# eDP_DLT.net
KiCad netlist of a schematic drawn in EAGLE
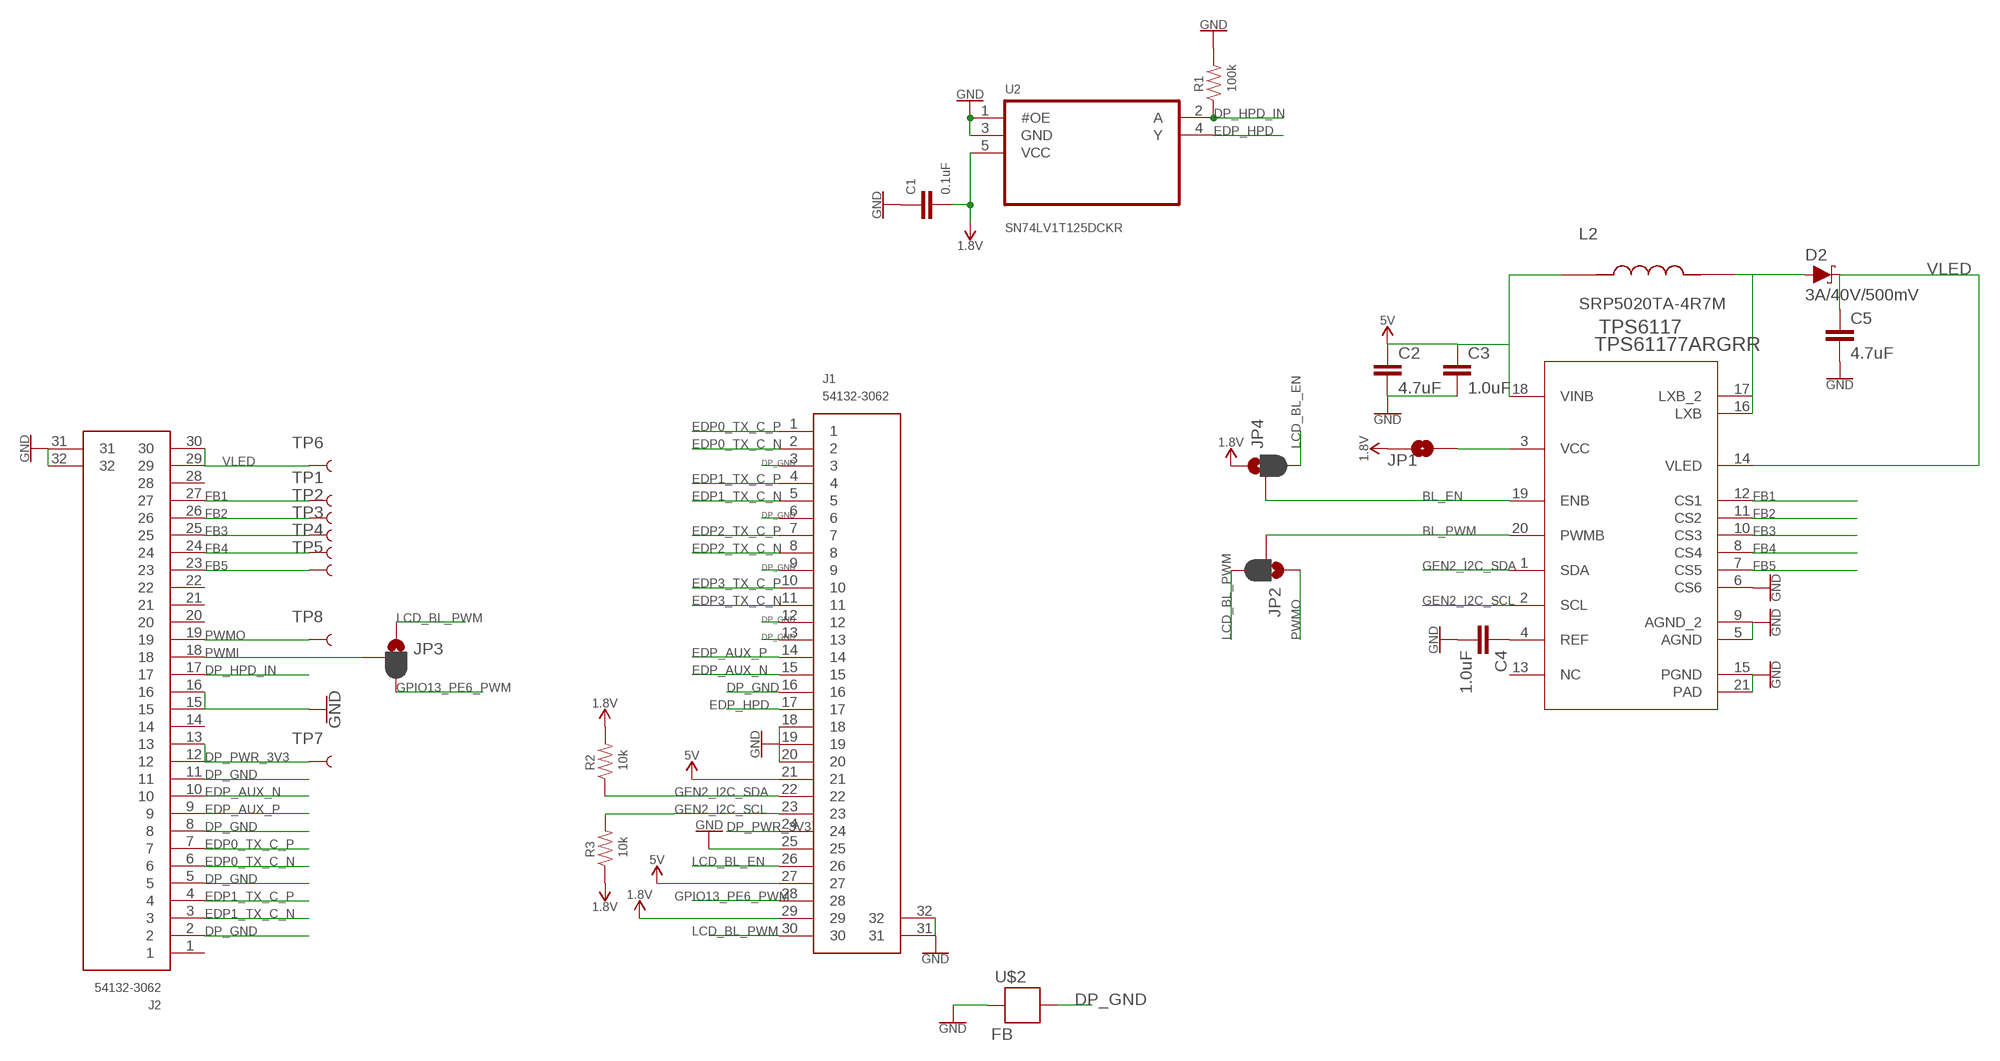
[diagram p0: schematic, sheet 1]

(export (version "E")
  (design (tool "Eeschema 10.0.6"))
  (components
    (comp (ref "C1")
      (value "0.1uF")
      (footprint "eagle-import:0603")
      (libsource (lib "eagle-import") (part "10NF-0603-50V-10%"))
    )
    (comp (ref "C2")
      (value "4.7uF")
      (footprint "eagle-import:0603")
      (libsource (lib "eagle-import") (part "4.7UF0603"))
    )
    (comp (ref "C3")
      (value "1.0uF")
      (footprint "eagle-import:0603")
      (libsource (lib "eagle-import") (part "1.0UF-0603-16V-10%"))
    )
    (comp (ref "C4")
      (value "1.0uF")
      (footprint "eagle-import:0603")
      (libsource (lib "eagle-import") (part "1.0UF-0603-16V-10%"))
    )
    (comp (ref "C5")
      (value "4.7uF")
      (footprint "eagle-import:0603")
      (libsource (lib "eagle-import") (part "4.7UF0603"))
    )
    (comp (ref "D2")
      (value "3A/40V/500mV")
      (footprint "eagle-import:SMA-DIODE")
      (libsource (lib "eagle-import") (part "DIODE-SCHOTTKY-B340A"))
    )
    (comp (ref "J1")
      (value "54132-3062")
      (footprint "eagle-import:54132-3062")
      (fields (field (name "MOUSER_PART_NUMBER") "538-54132-3062"))
      (libsource (lib "eagle-import") (part "54132-3062"))
    )
    (comp (ref "J2")
      (value "54132-3062")
      (footprint "eagle-import:54132-3062")
      (fields (field (name "MOUSER_PART_NUMBER") "538-54132-3062"))
      (libsource (lib "eagle-import") (part "54132-3062"))
    )
    (comp (ref "JP1")
      (value "JUMPER-SMT_2_NO_NO-SILK")
      (footprint "eagle-import:SMT-JUMPER_2_NO_NO-SILK")
      (libsource (lib "eagle-import") (part "JUMPER-SMT_2_NO_NO-SILK"))
    )
    (comp (ref "JP2")
      (value "JUMPER-SMT_3_1-NC_PASTE_NO-SILK")
      (footprint "eagle-import:SMT-JUMPER_3_1-NC_PASTE_NO-SILK")
      (libsource (lib "eagle-import") (part "JUMPER-SMT_3_1-NC_PASTE_NO-SILK"))
    )
    (comp (ref "JP3")
      (value "JUMPER-SMT_3_1-NC_PASTE_NO-SILK")
      (footprint "eagle-import:SMT-JUMPER_3_1-NC_PASTE_NO-SILK")
      (libsource (lib "eagle-import") (part "JUMPER-SMT_3_1-NC_PASTE_NO-SILK"))
    )
    (comp (ref "JP4")
      (value "JUMPER-SMT_3_1-NC_PASTE_NO-SILK")
      (footprint "eagle-import:SMT-JUMPER_3_1-NC_PASTE_NO-SILK")
      (libsource (lib "eagle-import") (part "JUMPER-SMT_3_1-NC_PASTE_NO-SILK"))
    )
    (comp (ref "L2")
      (value "SRP5020TA-4R7M")
      (footprint "eagle-import:IND_SRP5020TA-4R7M")
      (fields (field (name "MF") "Bourns"))
      (libsource (lib "eagle-import") (part "SRP5020TA-4R7M"))
    )
    (comp (ref "R1")
      (value "100k")
      (footprint "eagle-import:0603-RES")
      (libsource (lib "eagle-import") (part "RESISTOR0603-RES"))
    )
    (comp (ref "R2")
      (value "10k")
      (footprint "eagle-import:0603-RES")
      (libsource (lib "eagle-import") (part "RESISTOR0603-RES"))
    )
    (comp (ref "R3")
      (value "10k")
      (footprint "eagle-import:0603-RES")
      (libsource (lib "eagle-import") (part "RESISTOR0603-RES"))
    )
    (comp (ref "TP1")
      (value "TEST-POINT3")
      (footprint "eagle-import:PAD.03X.03")
      (libsource (lib "eagle-import") (part "TEST-POINT3"))
    )
    (comp (ref "TP2")
      (value "TEST-POINT3")
      (footprint "eagle-import:PAD.03X.03")
      (libsource (lib "eagle-import") (part "TEST-POINT3"))
    )
    (comp (ref "TP3")
      (value "TEST-POINT3")
      (footprint "eagle-import:PAD.03X.03")
      (libsource (lib "eagle-import") (part "TEST-POINT3"))
    )
    (comp (ref "TP4")
      (value "TEST-POINT3")
      (footprint "eagle-import:PAD.03X.03")
      (libsource (lib "eagle-import") (part "TEST-POINT3"))
    )
    (comp (ref "TP5")
      (value "TEST-POINT3")
      (footprint "eagle-import:PAD.03X.03")
      (libsource (lib "eagle-import") (part "TEST-POINT3"))
    )
    (comp (ref "TP6")
      (value "TEST-POINT3")
      (footprint "eagle-import:PAD.03X.03")
      (libsource (lib "eagle-import") (part "TEST-POINT3"))
    )
    (comp (ref "TP7")
      (value "TEST-POINT3")
      (footprint "eagle-import:PAD.03X.03")
      (libsource (lib "eagle-import") (part "TEST-POINT3"))
    )
    (comp (ref "TP8")
      (value "TEST-POINT3")
      (footprint "eagle-import:PAD.03X.03")
      (libsource (lib "eagle-import") (part "TEST-POINT3"))
    )
    (comp (ref "TPS6117")
      (value "TPS61177ARGRR")
      (footprint "eagle-import:RGR0020A")
      (libsource (lib "eagle-import") (part "TPS61177ARGRR"))
    )
    (comp (ref "U$2")
      (value "FB")
      (footprint "eagle-import:0603")
      (libsource (lib "eagle-import") (part "FB"))
    )
    (comp (ref "U2")
      (value "SN74LV1T125DCKR")
      (footprint "eagle-import:SOT65P210X110-5N")
      (fields (field (name "MF") "Texas Instruments"))
      (libsource (lib "eagle-import") (part "SN74LV1T125DCKR"))
    )
  )
  (nets
    (net (code "1") (name "/BL_EN") (class "Default")
      (node (ref "JP4") (pin "2") (pinfunction "2_2") (pintype "passive"))
      (node (ref "TPS6117") (pin "19") (pinfunction "ENB_19") (pintype "input"))
    )
    (net (code "2") (name "/BL_PWM") (class "Default")
      (node (ref "JP2") (pin "2") (pinfunction "2_2") (pintype "passive"))
      (node (ref "TPS6117") (pin "20") (pinfunction "PWMB_20") (pintype "input"))
    )
    (net (code "3") (name "/DP_GND") (class "Default")
      (node (ref "J1") (pin "12") (pinfunction "12_12") (pintype "bidirectional"))
      (node (ref "J1") (pin "13") (pinfunction "13_13") (pintype "bidirectional"))
      (node (ref "J1") (pin "16") (pinfunction "16_16") (pintype "bidirectional"))
      (node (ref "J1") (pin "3") (pinfunction "3_3") (pintype "bidirectional"))
      (node (ref "J1") (pin "6") (pinfunction "6_6") (pintype "bidirectional"))
      (node (ref "J1") (pin "9") (pinfunction "9_9") (pintype "bidirectional"))
      (node (ref "J2") (pin "11") (pinfunction "11_11") (pintype "bidirectional"))
      (node (ref "J2") (pin "2") (pinfunction "2_2") (pintype "bidirectional"))
      (node (ref "J2") (pin "5") (pinfunction "5_5") (pintype "bidirectional"))
      (node (ref "J2") (pin "8") (pinfunction "8_8") (pintype "bidirectional"))
      (node (ref "U$2") (pin "1") (pinfunction "P$1_1") (pintype "bidirectional"))
    )
    (net (code "4") (name "/DP_HPD_IN") (class "Default")
      (node (ref "J2") (pin "17") (pinfunction "17_17") (pintype "bidirectional"))
      (node (ref "R1") (pin "1") (pinfunction "1_1") (pintype "passive"))
      (node (ref "U2") (pin "2") (pinfunction "A_2") (pintype "output"))
    )
    (net (code "5") (name "/DP_PWR_3V3") (class "Default")
      (node (ref "J1") (pin "24") (pinfunction "24_24") (pintype "bidirectional"))
      (node (ref "J2") (pin "12") (pinfunction "12_12") (pintype "bidirectional"))
      (node (ref "J2") (pin "13") (pinfunction "13_13") (pintype "bidirectional"))
      (node (ref "TP7") (pin "P$1") (pinfunction "1_P$1") (pintype "bidirectional"))
    )
    (net (code "6") (name "/EDP0_TX_C_N") (class "Default")
      (node (ref "J1") (pin "2") (pinfunction "2_2") (pintype "bidirectional"))
      (node (ref "J2") (pin "6") (pinfunction "6_6") (pintype "bidirectional"))
    )
    (net (code "7") (name "/EDP0_TX_C_P") (class "Default")
      (node (ref "J1") (pin "1") (pinfunction "1_1") (pintype "bidirectional"))
      (node (ref "J2") (pin "7") (pinfunction "7_7") (pintype "bidirectional"))
    )
    (net (code "8") (name "/EDP1_TX_C_N") (class "Default")
      (node (ref "J1") (pin "5") (pinfunction "5_5") (pintype "bidirectional"))
      (node (ref "J2") (pin "3") (pinfunction "3_3") (pintype "bidirectional"))
    )
    (net (code "9") (name "/EDP1_TX_C_P") (class "Default")
      (node (ref "J1") (pin "4") (pinfunction "4_4") (pintype "bidirectional"))
      (node (ref "J2") (pin "4") (pinfunction "4_4") (pintype "bidirectional"))
    )
    (net (code "10") (name "/EDP2_TX_C_N") (class "Default")
      (node (ref "J1") (pin "8") (pinfunction "8_8") (pintype "bidirectional"))
    )
    (net (code "11") (name "/EDP2_TX_C_P") (class "Default")
      (node (ref "J1") (pin "7") (pinfunction "7_7") (pintype "bidirectional"))
    )
    (net (code "12") (name "/EDP3_TX_C_N") (class "Default")
      (node (ref "J1") (pin "11") (pinfunction "11_11") (pintype "bidirectional"))
    )
    (net (code "13") (name "/EDP3_TX_C_P") (class "Default")
      (node (ref "J1") (pin "10") (pinfunction "10_10") (pintype "bidirectional"))
    )
    (net (code "14") (name "/EDP_AUX_N") (class "Default")
      (node (ref "J1") (pin "15") (pinfunction "15_15") (pintype "bidirectional"))
      (node (ref "J2") (pin "10") (pinfunction "10_10") (pintype "bidirectional"))
    )
    (net (code "15") (name "/EDP_AUX_P") (class "Default")
      (node (ref "J1") (pin "14") (pinfunction "14_14") (pintype "bidirectional"))
      (node (ref "J2") (pin "9") (pinfunction "9_9") (pintype "bidirectional"))
    )
    (net (code "16") (name "/EDP_HPD") (class "Default")
      (node (ref "J1") (pin "17") (pinfunction "17_17") (pintype "bidirectional"))
      (node (ref "U2") (pin "4") (pinfunction "Y_4") (pintype "output"))
    )
    (net (code "17") (name "/FB1") (class "Default")
      (node (ref "J2") (pin "27") (pinfunction "27_27") (pintype "bidirectional"))
      (node (ref "TP1") (pin "P$1") (pinfunction "1_P$1") (pintype "bidirectional"))
      (node (ref "TPS6117") (pin "12") (pinfunction "CS1_12") (pintype "power_in"))
    )
    (net (code "18") (name "/FB2") (class "Default")
      (node (ref "J2") (pin "26") (pinfunction "26_26") (pintype "bidirectional"))
      (node (ref "TP2") (pin "P$1") (pinfunction "1_P$1") (pintype "bidirectional"))
      (node (ref "TPS6117") (pin "11") (pinfunction "CS2_11") (pintype "power_in"))
    )
    (net (code "19") (name "/FB3") (class "Default")
      (node (ref "J2") (pin "25") (pinfunction "25_25") (pintype "bidirectional"))
      (node (ref "TP3") (pin "P$1") (pinfunction "1_P$1") (pintype "bidirectional"))
      (node (ref "TPS6117") (pin "10") (pinfunction "CS3_10") (pintype "power_in"))
    )
    (net (code "20") (name "/FB4") (class "Default")
      (node (ref "J2") (pin "24") (pinfunction "24_24") (pintype "bidirectional"))
      (node (ref "TP4") (pin "P$1") (pinfunction "1_P$1") (pintype "bidirectional"))
      (node (ref "TPS6117") (pin "8") (pinfunction "CS4_8") (pintype "power_in"))
    )
    (net (code "21") (name "/FB5") (class "Default")
      (node (ref "J2") (pin "23") (pinfunction "23_23") (pintype "bidirectional"))
      (node (ref "TP5") (pin "P$1") (pinfunction "1_P$1") (pintype "bidirectional"))
      (node (ref "TPS6117") (pin "7") (pinfunction "CS5_7") (pintype "power_in"))
    )
    (net (code "22") (name "/GEN2_I2C_SCL") (class "Default")
      (node (ref "J1") (pin "23") (pinfunction "23_23") (pintype "bidirectional"))
      (node (ref "R3") (pin "2") (pinfunction "2_2") (pintype "passive"))
      (node (ref "TPS6117") (pin "2") (pinfunction "SCL_2") (pintype "input"))
    )
    (net (code "23") (name "/GEN2_I2C_SDA") (class "Default")
      (node (ref "J1") (pin "22") (pinfunction "22_22") (pintype "bidirectional"))
      (node (ref "R2") (pin "1") (pinfunction "1_1") (pintype "passive"))
      (node (ref "TPS6117") (pin "1") (pinfunction "SDA_1") (pintype "input"))
    )
    (net (code "24") (name "/GPIO13_PE6_PWM") (class "Default")
      (node (ref "J1") (pin "28") (pinfunction "28_28") (pintype "bidirectional"))
      (node (ref "JP3") (pin "3") (pinfunction "3_3") (pintype "passive"))
    )
    (net (code "25") (name "/LCD_BL_EN") (class "Default")
      (node (ref "J1") (pin "26") (pinfunction "26_26") (pintype "bidirectional"))
      (node (ref "JP4") (pin "3") (pinfunction "3_3") (pintype "passive"))
    )
    (net (code "26") (name "/LCD_BL_PWM") (class "Default")
      (node (ref "J1") (pin "30") (pinfunction "30_30") (pintype "bidirectional"))
      (node (ref "JP2") (pin "3") (pinfunction "3_3") (pintype "passive"))
      (node (ref "JP3") (pin "1") (pinfunction "1_1") (pintype "passive"))
    )
    (net (code "27") (name "/PWMI") (class "Default")
      (node (ref "J2") (pin "18") (pinfunction "18_18") (pintype "bidirectional"))
      (node (ref "JP3") (pin "2") (pinfunction "2_2") (pintype "passive"))
    )
    (net (code "28") (name "/PWMO") (class "Default")
      (node (ref "J2") (pin "19") (pinfunction "19_19") (pintype "bidirectional"))
      (node (ref "JP2") (pin "1") (pinfunction "1_1") (pintype "passive"))
      (node (ref "TP8") (pin "P$1") (pinfunction "1_P$1") (pintype "bidirectional"))
    )
    (net (code "29") (name "/VLED") (class "Default")
      (node (ref "C5") (pin "1") (pinfunction "1_1") (pintype "passive"))
      (node (ref "D2") (pin "C") (pinfunction "C_C") (pintype "passive"))
      (node (ref "J2") (pin "29") (pinfunction "29_29") (pintype "bidirectional"))
      (node (ref "J2") (pin "30") (pinfunction "30_30") (pintype "bidirectional"))
      (node (ref "TP6") (pin "P$1") (pinfunction "1_P$1") (pintype "bidirectional"))
      (node (ref "TPS6117") (pin "14") (pinfunction "VLED_14") (pintype "input"))
    )
    (net (code "30") (name "1.8V") (class "Default")
      (node (ref "C1") (pin "2") (pinfunction "2_2") (pintype "passive"))
      (node (ref "J1") (pin "29") (pinfunction "29_29") (pintype "bidirectional"))
      (node (ref "JP1") (pin "1") (pinfunction "1_1") (pintype "passive"))
      (node (ref "JP4") (pin "1") (pinfunction "1_1") (pintype "passive"))
      (node (ref "R2") (pin "2") (pinfunction "2_2") (pintype "passive"))
      (node (ref "R3") (pin "1") (pinfunction "1_1") (pintype "passive"))
      (node (ref "U2") (pin "5") (pinfunction "VCC_5") (pintype "input"))
    )
    (net (code "31") (name "5V") (class "Default")
      (node (ref "C2") (pin "1") (pinfunction "1_1") (pintype "passive"))
      (node (ref "C3") (pin "1") (pinfunction "1_1") (pintype "passive"))
      (node (ref "J1") (pin "21") (pinfunction "21_21") (pintype "bidirectional"))
      (node (ref "J1") (pin "27") (pinfunction "27_27") (pintype "bidirectional"))
      (node (ref "L2") (pin "1") (pinfunction "1_1") (pintype "passive"))
      (node (ref "TPS6117") (pin "18") (pinfunction "VINB_18") (pintype "power_in"))
    )
    (net (code "32") (name "GND") (class "Default")
      (node (ref "C1") (pin "1") (pinfunction "1_1") (pintype "passive"))
      (node (ref "C2") (pin "2") (pinfunction "2_2") (pintype "passive"))
      (node (ref "C3") (pin "2") (pinfunction "2_2") (pintype "passive"))
      (node (ref "C4") (pin "2") (pinfunction "2_2") (pintype "passive"))
      (node (ref "C5") (pin "2") (pinfunction "2_2") (pintype "passive"))
      (node (ref "J1") (pin "18") (pinfunction "18_18") (pintype "bidirectional"))
      (node (ref "J1") (pin "19") (pinfunction "19_19") (pintype "bidirectional"))
      (node (ref "J1") (pin "20") (pinfunction "20_20") (pintype "bidirectional"))
      (node (ref "J1") (pin "25") (pinfunction "25_25") (pintype "bidirectional"))
      (node (ref "J1") (pin "31") (pinfunction "31_31") (pintype "bidirectional"))
      (node (ref "J1") (pin "32") (pinfunction "32_32") (pintype "bidirectional"))
      (node (ref "J2") (pin "15") (pinfunction "15_15") (pintype "bidirectional"))
      (node (ref "J2") (pin "16") (pinfunction "16_16") (pintype "bidirectional"))
      (node (ref "J2") (pin "31") (pinfunction "31_31") (pintype "bidirectional"))
      (node (ref "J2") (pin "32") (pinfunction "32_32") (pintype "bidirectional"))
      (node (ref "R1") (pin "2") (pinfunction "2_2") (pintype "passive"))
      (node (ref "TPS6117") (pin "15") (pinfunction "PGND_15") (pintype "power_in"))
      (node (ref "TPS6117") (pin "21") (pinfunction "PAD_21") (pintype "power_in"))
      (node (ref "TPS6117") (pin "5") (pinfunction "AGND_5") (pintype "power_in"))
      (node (ref "TPS6117") (pin "6") (pinfunction "CS6_6") (pintype "power_in"))
      (node (ref "TPS6117") (pin "9") (pinfunction "AGND_2_9") (pintype "power_in"))
      (node (ref "U$2") (pin "2") (pinfunction "P$2_2") (pintype "bidirectional"))
      (node (ref "U2") (pin "1") (pinfunction "#OE_1") (pintype "input"))
      (node (ref "U2") (pin "3") (pinfunction "GND_3") (pintype "input"))
    )
    (net (code "33") (name "Net-(TPS6117-LXB)") (class "Default")
      (node (ref "D2") (pin "A") (pinfunction "A_A") (pintype "passive"))
      (node (ref "L2") (pin "2") (pinfunction "2_2") (pintype "passive"))
      (node (ref "TPS6117") (pin "16") (pinfunction "LXB_16") (pintype "power_in"))
      (node (ref "TPS6117") (pin "17") (pinfunction "LXB_2_17") (pintype "power_in"))
    )
    (net (code "34") (name "Net-(TPS6117-REF)") (class "Default")
      (node (ref "C4") (pin "1") (pinfunction "1_1") (pintype "passive"))
      (node (ref "TPS6117") (pin "4") (pinfunction "REF_4") (pintype "input"))
    )
    (net (code "35") (name "Net-(TPS6117-VCC)") (class "Default")
      (node (ref "JP1") (pin "2") (pinfunction "2_2") (pintype "passive"))
      (node (ref "TPS6117") (pin "3") (pinfunction "VCC_3") (pintype "power_in"))
    )
    (net (code "36") (name "unconnected-(J2-Pad1)") (class "Default")
      (node (ref "J2") (pin "1") (pinfunction "1_1") (pintype "bidirectional"))
    )
    (net (code "37") (name "unconnected-(J2-Pad14)") (class "Default")
      (node (ref "J2") (pin "14") (pinfunction "14_14") (pintype "bidirectional"))
    )
    (net (code "38") (name "unconnected-(J2-Pad20)") (class "Default")
      (node (ref "J2") (pin "20") (pinfunction "20_20") (pintype "bidirectional"))
    )
    (net (code "39") (name "unconnected-(J2-Pad21)") (class "Default")
      (node (ref "J2") (pin "21") (pinfunction "21_21") (pintype "bidirectional"))
    )
    (net (code "40") (name "unconnected-(J2-Pad22)") (class "Default")
      (node (ref "J2") (pin "22") (pinfunction "22_22") (pintype "bidirectional"))
    )
    (net (code "41") (name "unconnected-(J2-Pad28)") (class "Default")
      (node (ref "J2") (pin "28") (pinfunction "28_28") (pintype "bidirectional"))
    )
    (net (code "42") (name "unconnected-(TPS6117-NC-Pad13)") (class "Default")
      (node (ref "TPS6117") (pin "13") (pinfunction "NC_13") (pintype "passive"))
    )
  )
)
